# Qwiic_Flex_Glove_Controller.net
KiCad netlist of a schematic drawn in EAGLE
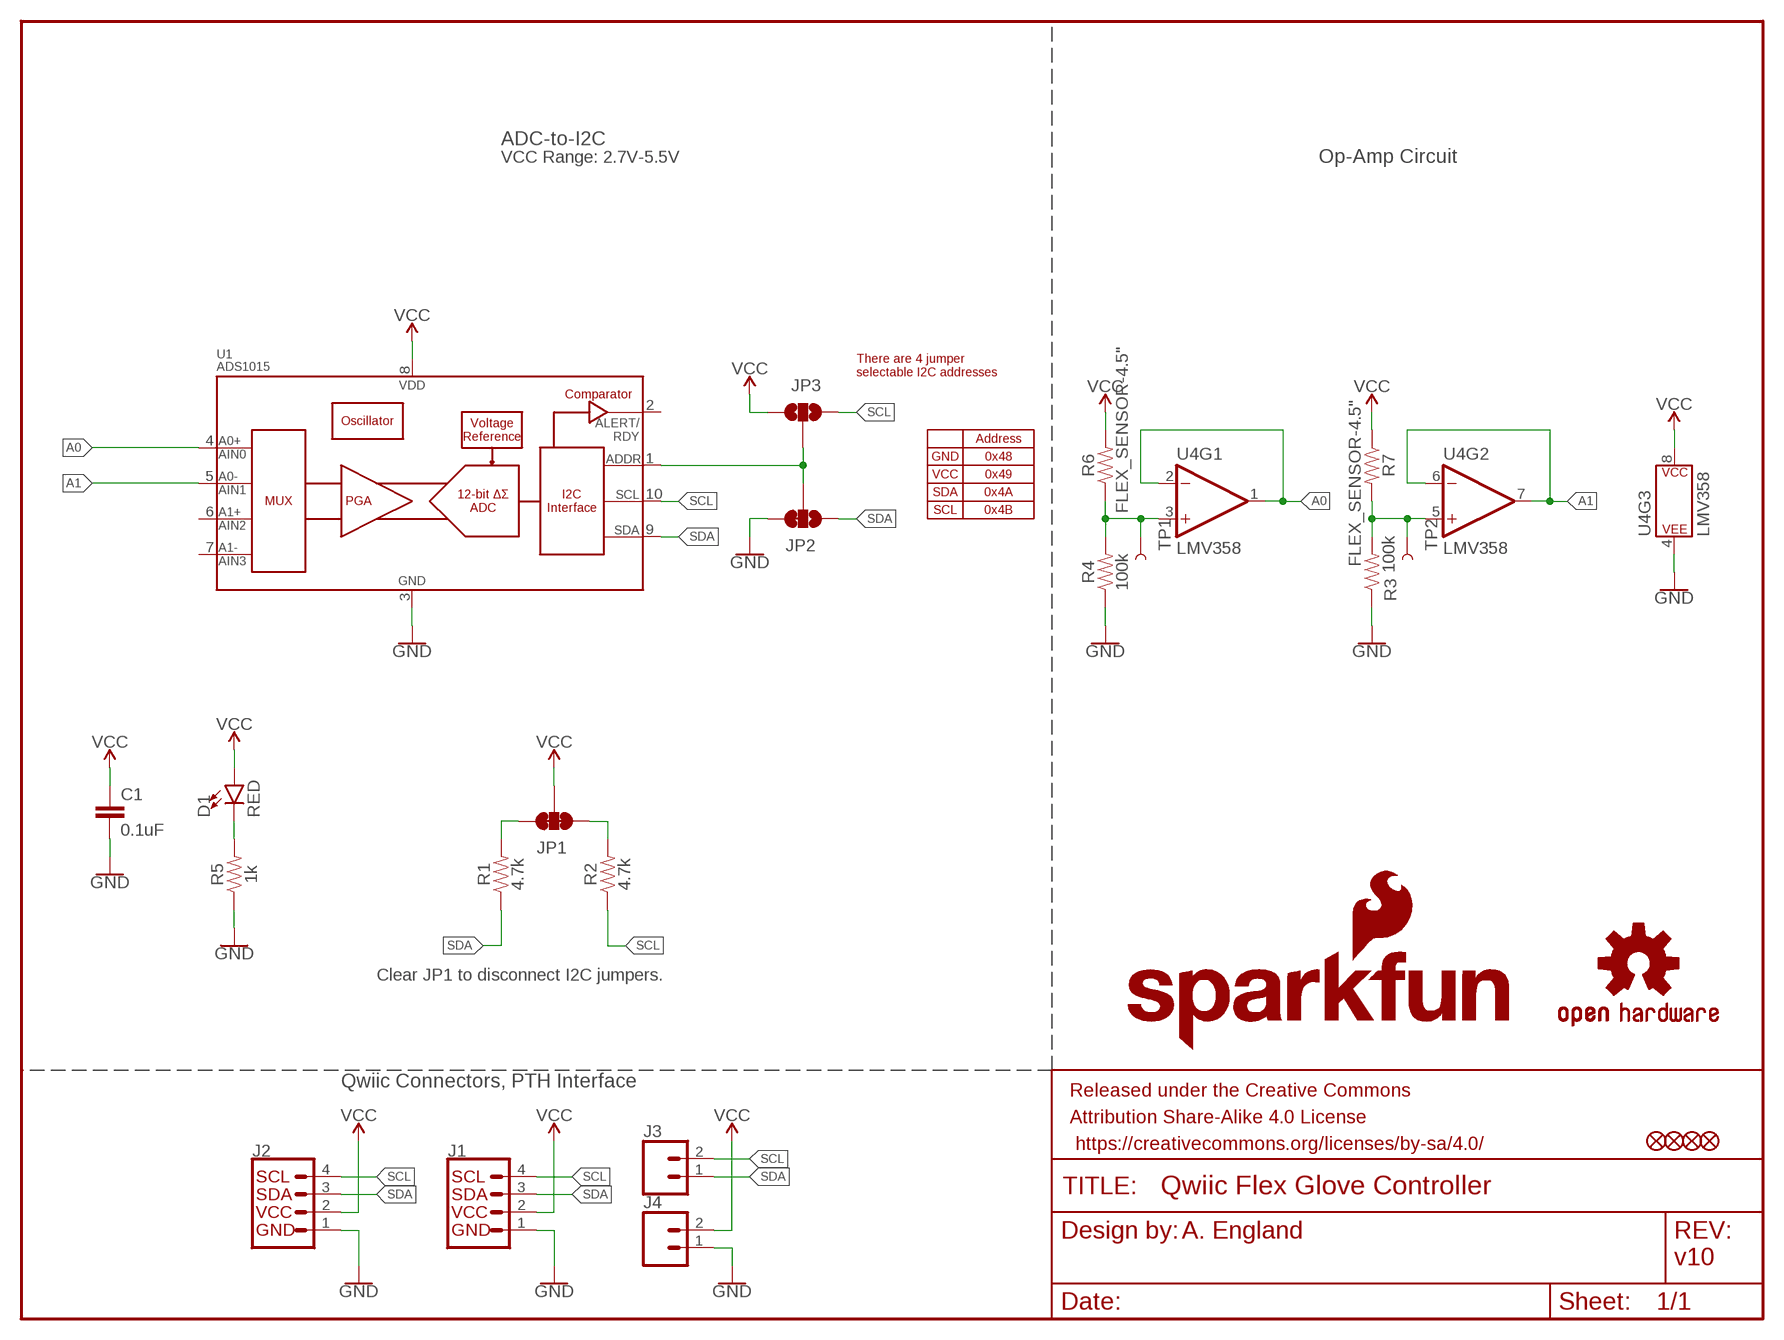
[diagram p0: schematic, sheet 1]

(export (version "E")
  (design (tool "Eeschema 10.0.6"))
  (components
    (comp (ref "C1")
      (value "0.1uF")
      (footprint "eagle-import:0603")
      (libsource (lib "eagle-import") (part "0.1UF-0603-25V-(+80/-20%)"))
    )
    (comp (ref "D1")
      (value "RED")
      (footprint "eagle-import:LED-0603")
      (libsource (lib "eagle-import") (part "LED-RED0603"))
    )
    (comp (ref "FD1")
      (value "FIDUCIALUFIDUCIAL")
      (footprint "eagle-import:FIDUCIAL-MICRO")
      (libsource (lib "eagle-import") (part "FIDUCIALUFIDUCIAL"))
    )
    (comp (ref "FD2")
      (value "FIDUCIALUFIDUCIAL")
      (footprint "eagle-import:FIDUCIAL-MICRO")
      (libsource (lib "eagle-import") (part "FIDUCIALUFIDUCIAL"))
    )
    (comp (ref "FD3")
      (value "FIDUCIALUFIDUCIAL")
      (footprint "eagle-import:FIDUCIAL-MICRO")
      (libsource (lib "eagle-import") (part "FIDUCIALUFIDUCIAL"))
    )
    (comp (ref "FD4")
      (value "FIDUCIALUFIDUCIAL")
      (footprint "eagle-import:FIDUCIAL-MICRO")
      (libsource (lib "eagle-import") (part "FIDUCIALUFIDUCIAL"))
    )
    (comp (ref "FRAME1")
      (value "FRAME-LETTER")
      (footprint "eagle-import:CREATIVE_COMMONS")
      (libsource (lib "eagle-import") (part "FRAME-LETTER"))
    )
    (comp (ref "J1")
      (value "QWIIC_CONNECTORJS-1MM")
      (footprint "eagle-import:1X04_1MM_RA")
      (libsource (lib "eagle-import") (part "QWIIC_CONNECTORJS-1MM"))
    )
    (comp (ref "J2")
      (value "QWIIC_CONNECTORJS-1MM")
      (footprint "eagle-import:1X04_1MM_RA")
      (libsource (lib "eagle-import") (part "QWIIC_CONNECTORJS-1MM"))
    )
    (comp (ref "J3")
      (value "CONN_02")
      (footprint "eagle-import:1X02")
      (libsource (lib "eagle-import") (part "CONN_02"))
    )
    (comp (ref "J4")
      (value "CONN_02")
      (footprint "eagle-import:1X02")
      (libsource (lib "eagle-import") (part "CONN_02"))
    )
    (comp (ref "JP1")
      (value "JUMPER-SMT_3_2-NC_TRACE_NO-SILK")
      (footprint "eagle-import:SMT-JUMPER_3_2-NC_TRACE_NO-SILK")
      (libsource (lib "eagle-import") (part "JUMPER-SMT_3_2-NC_TRACE_NO-SILK"))
    )
    (comp (ref "JP2")
      (value "JUMPER-SMT_3_1-NC_TRACE_NO-SILK")
      (footprint "eagle-import:SMT-JUMPER_3_1-NC_TRACE_NO-SILK")
      (libsource (lib "eagle-import") (part "JUMPER-SMT_3_1-NC_TRACE_NO-SILK"))
    )
    (comp (ref "JP3")
      (value "JUMPER-SMT_3_NO_NO_SILK")
      (footprint "eagle-import:SMT-JUMPER_3_0-NO_TRACE_NO-SILK")
      (libsource (lib "eagle-import") (part "JUMPER-SMT_3_NO_NO_SILK"))
    )
    (comp (ref "LOGO1")
      (value "SFE_LOGO_NAME_FLAME.1_INCH")
      (footprint "eagle-import:SFE_LOGO_NAME_FLAME_.1")
      (libsource (lib "eagle-import") (part "SFE_LOGO_NAME_FLAME.1_INCH"))
    )
    (comp (ref "LOGO2")
      (value "OSHW-LOGOS")
      (footprint "eagle-import:OSHW-LOGO-S")
      (libsource (lib "eagle-import") (part "OSHW-LOGOS"))
    )
    (comp (ref "LOGO3")
      (value "SFE_LOGO_FLAME.1_INCH")
      (footprint "eagle-import:SFE_LOGO_FLAME_.1")
      (libsource (lib "eagle-import") (part "SFE_LOGO_FLAME.1_INCH"))
    )
    (comp (ref "R1")
      (value "4.7k")
      (footprint "eagle-import:0603")
      (libsource (lib "eagle-import") (part "4.7KOHM-0603-1/10W-1%"))
    )
    (comp (ref "R2")
      (value "4.7k")
      (footprint "eagle-import:0603")
      (libsource (lib "eagle-import") (part "4.7KOHM-0603-1/10W-1%"))
    )
    (comp (ref "R3")
      (value "100k")
      (footprint "eagle-import:0603")
      (libsource (lib "eagle-import") (part "100KOHM-0603-1/10W-1%"))
    )
    (comp (ref "R4")
      (value "100k")
      (footprint "eagle-import:0603")
      (libsource (lib "eagle-import") (part "100KOHM-0603-1/10W-1%"))
    )
    (comp (ref "R5")
      (value "1k")
      (footprint "eagle-import:0603")
      (libsource (lib "eagle-import") (part "1KOHM-0603-1/10W-1%"))
    )
    (comp (ref "R6")
      (value "FLEX_SENSOR-4.5\"")
      (footprint "eagle-import:FLEX_SENSOR")
      (libsource (lib "eagle-import") (part "FLEX_SENSOR-4.5{dblquote}"))
    )
    (comp (ref "R7")
      (value "FLEX_SENSOR-4.5\"")
      (footprint "eagle-import:FLEX_SENSOR")
      (libsource (lib "eagle-import") (part "FLEX_SENSOR-4.5{dblquote}"))
    )
    (comp (ref "TP1")
      (value "TEST-POINT3")
      (footprint "eagle-import:PAD.03X.03")
      (libsource (lib "eagle-import") (part "TEST-POINT3"))
    )
    (comp (ref "TP2")
      (value "TEST-POINT3")
      (footprint "eagle-import:PAD.03X.03")
      (libsource (lib "eagle-import") (part "TEST-POINT3"))
    )
    (comp (ref "U1")
      (value "ADS1015")
      (footprint "eagle-import:MSOP10")
      (libsource (lib "eagle-import") (part "ADS1015"))
    )
    (comp (ref "U4")
      (value "LMV358")
      (footprint "eagle-import:SO08")
      (libsource (lib "eagle-import") (part "LMV358SOIC"))
    )
  )
  (nets
    (net (code "1") (name "A0") (class "Default")
      (node (ref "U1") (pin "4") (pinfunction "AIN0_4") (pintype "bidirectional"))
      (node (ref "U4") (pin "1") (pinfunction "OUT_1") (pintype "output"))
      (node (ref "U4") (pin "2") (pinfunction "-IN_2") (pintype "input"))
    )
    (net (code "2") (name "A1") (class "Default")
      (node (ref "U1") (pin "5") (pinfunction "AIN1_5") (pintype "bidirectional"))
      (node (ref "U4") (pin "6") (pinfunction "-IN_6") (pintype "input"))
      (node (ref "U4") (pin "7") (pinfunction "OUT_7") (pintype "output"))
    )
    (net (code "3") (name "GND") (class "Default")
      (node (ref "C1") (pin "2") (pinfunction "2_2") (pintype "passive"))
      (node (ref "J1") (pin "1") (pinfunction "1_1") (pintype "power_in"))
      (node (ref "J2") (pin "1") (pinfunction "1_1") (pintype "power_in"))
      (node (ref "J4") (pin "1") (pinfunction "1_1") (pintype "passive"))
      (node (ref "JP2") (pin "3") (pinfunction "3_3") (pintype "passive"))
      (node (ref "R3") (pin "1") (pinfunction "1_1") (pintype "passive"))
      (node (ref "R4") (pin "1") (pinfunction "1_1") (pintype "passive"))
      (node (ref "R5") (pin "1") (pinfunction "1_1") (pintype "passive"))
      (node (ref "U1") (pin "3") (pinfunction "VSS_3") (pintype "bidirectional"))
      (node (ref "U4") (pin "4") (pinfunction "P$V-_4") (pintype "bidirectional"))
    )
    (net (code "4") (name "Net-(D1-PadC)") (class "Default")
      (node (ref "D1") (pin "C") (pinfunction "C_C") (pintype "passive"))
      (node (ref "R5") (pin "2") (pinfunction "2_2") (pintype "passive"))
    )
    (net (code "5") (name "Net-(JP1-Pad1)") (class "Default")
      (node (ref "JP1") (pin "1") (pinfunction "1_1") (pintype "passive"))
      (node (ref "R2") (pin "2") (pinfunction "2_2") (pintype "passive"))
    )
    (net (code "6") (name "Net-(JP1-Pad3)") (class "Default")
      (node (ref "JP1") (pin "3") (pinfunction "3_3") (pintype "passive"))
      (node (ref "R1") (pin "2") (pinfunction "2_2") (pintype "passive"))
    )
    (net (code "7") (name "Net-(R6-1)") (class "Default")
      (node (ref "R4") (pin "2") (pinfunction "2_2") (pintype "passive"))
      (node (ref "R6") (pin "P$1") (pinfunction "1_P$1") (pintype "passive"))
      (node (ref "TP1") (pin "P$1") (pinfunction "1_P$1") (pintype "bidirectional"))
      (node (ref "U4") (pin "3") (pinfunction "+IN_3") (pintype "input"))
    )
    (net (code "8") (name "Net-(R7-2)") (class "Default")
      (node (ref "R3") (pin "2") (pinfunction "2_2") (pintype "passive"))
      (node (ref "R7") (pin "P$2") (pinfunction "2_P$2") (pintype "passive"))
      (node (ref "TP2") (pin "P$1") (pinfunction "1_P$1") (pintype "bidirectional"))
      (node (ref "U4") (pin "5") (pinfunction "+IN_5") (pintype "input"))
    )
    (net (code "9") (name "Net-(U1-ADDR)") (class "Default")
      (node (ref "JP2") (pin "2") (pinfunction "2_2") (pintype "passive"))
      (node (ref "JP3") (pin "2") (pinfunction "2_2") (pintype "passive"))
      (node (ref "U1") (pin "1") (pinfunction "ADDR_1") (pintype "bidirectional"))
    )
    (net (code "10") (name "SCL") (class "Default")
      (node (ref "J1") (pin "4") (pinfunction "4_4") (pintype "passive"))
      (node (ref "J2") (pin "4") (pinfunction "4_4") (pintype "passive"))
      (node (ref "J3") (pin "2") (pinfunction "2_2") (pintype "passive"))
      (node (ref "JP3") (pin "3") (pinfunction "3_3") (pintype "passive"))
      (node (ref "R2") (pin "1") (pinfunction "1_1") (pintype "passive"))
      (node (ref "U1") (pin "10") (pinfunction "SCL_10") (pintype "bidirectional"))
    )
    (net (code "11") (name "SDA") (class "Default")
      (node (ref "J1") (pin "3") (pinfunction "3_3") (pintype "passive"))
      (node (ref "J2") (pin "3") (pinfunction "3_3") (pintype "passive"))
      (node (ref "J3") (pin "1") (pinfunction "1_1") (pintype "passive"))
      (node (ref "JP2") (pin "1") (pinfunction "1_1") (pintype "passive"))
      (node (ref "R1") (pin "1") (pinfunction "1_1") (pintype "passive"))
      (node (ref "U1") (pin "9") (pinfunction "SDA_9") (pintype "bidirectional"))
    )
    (net (code "12") (name "VCC") (class "Default")
      (node (ref "C1") (pin "1") (pinfunction "1_1") (pintype "passive"))
      (node (ref "D1") (pin "A") (pinfunction "A_A") (pintype "passive"))
      (node (ref "J1") (pin "2") (pinfunction "2_2") (pintype "power_in"))
      (node (ref "J2") (pin "2") (pinfunction "2_2") (pintype "power_in"))
      (node (ref "J4") (pin "2") (pinfunction "2_2") (pintype "passive"))
      (node (ref "JP1") (pin "2") (pinfunction "2_2") (pintype "passive"))
      (node (ref "JP3") (pin "1") (pinfunction "1_1") (pintype "passive"))
      (node (ref "R6") (pin "P$2") (pinfunction "2_P$2") (pintype "passive"))
      (node (ref "R7") (pin "P$1") (pinfunction "1_P$1") (pintype "passive"))
      (node (ref "U1") (pin "8") (pinfunction "VDD_8") (pintype "bidirectional"))
      (node (ref "U4") (pin "8") (pinfunction "P$V+_8") (pintype "bidirectional"))
    )
    (net (code "13") (name "unconnected-(U1-AIN2-Pad6)") (class "Default")
      (node (ref "U1") (pin "6") (pinfunction "AIN2_6") (pintype "bidirectional"))
    )
    (net (code "14") (name "unconnected-(U1-AIN3-Pad7)") (class "Default")
      (node (ref "U1") (pin "7") (pinfunction "AIN3_7") (pintype "bidirectional"))
    )
    (net (code "15") (name "unconnected-(U1-ALERT{slash}RDY-Pad2)") (class "Default")
      (node (ref "U1") (pin "2") (pinfunction "ALERT/RDY_2") (pintype "bidirectional"))
    )
  )
)
